# Board.net
KiCad netlist of a schematic drawn in EAGLE
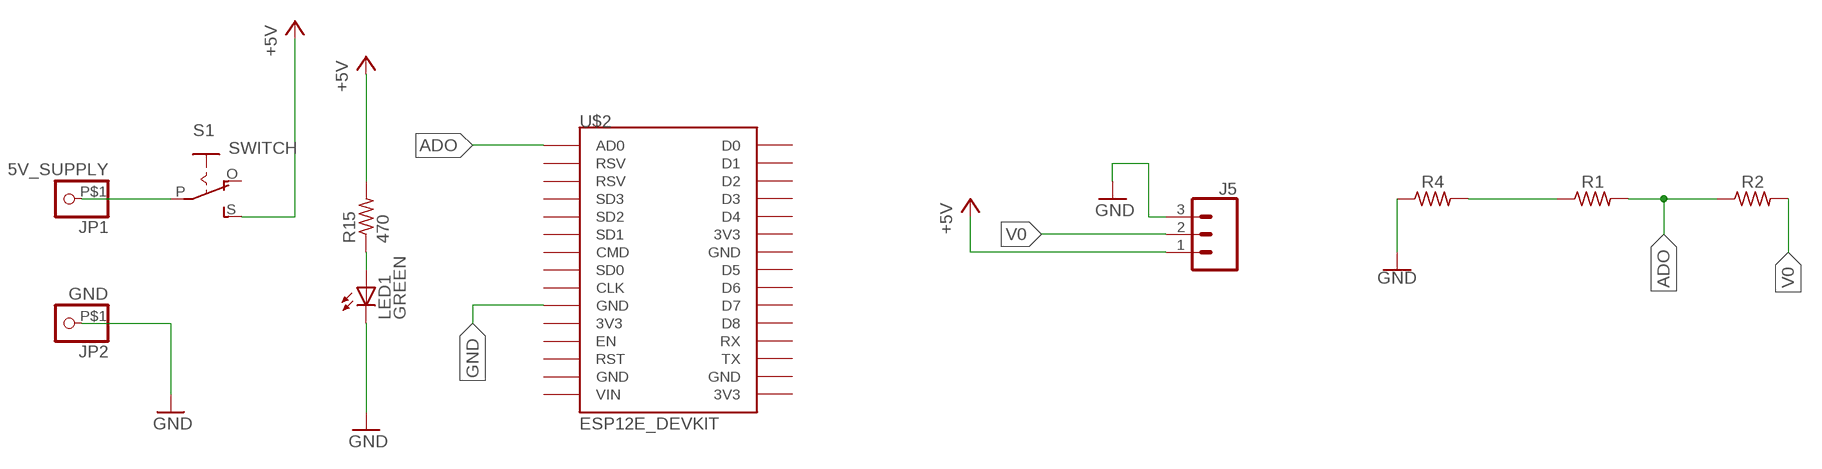
[diagram p0: schematic, sheet 1]

(export (version "E")
  (design (tool "Eeschema 10.0.6"))
  (components
    (comp (ref "J5")
      (value "1x3 RA Female .1\"")
      (footprint "eagle-import:1X03")
      (libsource (lib "eagle-import") (part "CONN_03"))
    )
    (comp (ref "JP1")
      (value "5V_SUPPLY")
      (footprint "eagle-import:1X1-BIGPOGO")
      (libsource (lib "eagle-import") (part "PINHD-1X1-BIGPOGO"))
    )
    (comp (ref "JP2")
      (value "GND")
      (footprint "eagle-import:1X1-BIGPOGO")
      (libsource (lib "eagle-import") (part "PINHD-1X1-BIGPOGO"))
    )
    (comp (ref "LED1")
      (value "GREEN")
      (footprint "eagle-import:LED5MM")
      (libsource (lib "eagle-import") (part "LED5MM"))
    )
    (comp (ref "R1")
      (value "101")
      (footprint "eagle-import:0207_12")
      (libsource (lib "eagle-import") (part "R-US_0207/12"))
    )
    (comp (ref "R2")
      (value "10k")
      (footprint "eagle-import:0207_12")
      (libsource (lib "eagle-import") (part "R-US_0207/12"))
    )
    (comp (ref "R4")
      (value "2.4k")
      (footprint "eagle-import:0207_12")
      (libsource (lib "eagle-import") (part "R-US_0207/12"))
    )
    (comp (ref "R15")
      (value "470")
      (footprint "eagle-import:0207_12")
      (libsource (lib "eagle-import") (part "R-US_0207/12"))
    )
    (comp (ref "S1")
      (value "SWITCH")
      (footprint "eagle-import:EG1218")
      (libsource (lib "eagle-import") (part "EG1218S"))
    )
    (comp (ref "U$2")
      (value "ESP12E_DEVKIT")
      (footprint "eagle-import:ESP12E_DEVKIT")
      (libsource (lib "eagle-import") (part "ESP12E_DEVKIT"))
    )
  )
  (nets
    (net (code "1") (name "+5V") (class "Default")
      (node (ref "J5") (pin "1") (pinfunction "1_1") (pintype "passive"))
      (node (ref "R15") (pin "2") (pinfunction "2_2") (pintype "passive"))
      (node (ref "S1") (pin "S") (pinfunction "S_S") (pintype "passive"))
    )
    (net (code "2") (name "ADO") (class "Default")
      (node (ref "R1") (pin "2") (pinfunction "2_2") (pintype "passive"))
      (node (ref "R2") (pin "1") (pinfunction "1_1") (pintype "passive"))
      (node (ref "U$2") (pin "AD0") (pinfunction "AD0_AD0") (pintype "bidirectional"))
    )
    (net (code "3") (name "GND") (class "Default")
      (node (ref "J5") (pin "3") (pinfunction "3_3") (pintype "passive"))
      (node (ref "JP2") (pin "P$1") (pinfunction "1_P$1") (pintype "passive"))
      (node (ref "LED1") (pin "K") (pinfunction "C_K") (pintype "passive"))
      (node (ref "R4") (pin "1") (pinfunction "1_1") (pintype "passive"))
      (node (ref "U$2") (pin "GND@0") (pinfunction "GND_GND@0") (pintype "bidirectional"))
    )
    (net (code "4") (name "Net-(JP1-1)") (class "Default")
      (node (ref "JP1") (pin "P$1") (pinfunction "1_P$1") (pintype "passive"))
      (node (ref "S1") (pin "P") (pinfunction "P_P") (pintype "passive"))
    )
    (net (code "5") (name "Net-(LED1-PadA)") (class "Default")
      (node (ref "LED1") (pin "A") (pinfunction "A_A") (pintype "passive"))
      (node (ref "R15") (pin "1") (pinfunction "1_1") (pintype "passive"))
    )
    (net (code "6") (name "Net-(R1-Pad1)") (class "Default")
      (node (ref "R1") (pin "1") (pinfunction "1_1") (pintype "passive"))
      (node (ref "R4") (pin "2") (pinfunction "2_2") (pintype "passive"))
    )
    (net (code "7") (name "V0") (class "Default")
      (node (ref "J5") (pin "2") (pinfunction "2_2") (pintype "passive"))
      (node (ref "R2") (pin "2") (pinfunction "2_2") (pintype "passive"))
    )
    (net (code "8") (name "unconnected-(S1-PadO)") (class "Default")
      (node (ref "S1") (pin "O") (pinfunction "O_O") (pintype "passive"))
    )
    (net (code "9") (name "unconnected-(U$2-3V3-Pad3V3@0)") (class "Default")
      (node (ref "U$2") (pin "3V3@0") (pinfunction "3V3_3V3@0") (pintype "bidirectional"))
    )
    (net (code "10") (name "unconnected-(U$2-3V3-Pad3V3@1)") (class "Default")
      (node (ref "U$2") (pin "3V3@1") (pinfunction "3V3_3V3@1") (pintype "bidirectional"))
    )
    (net (code "11") (name "unconnected-(U$2-3V3-Pad3V3@2)") (class "Default")
      (node (ref "U$2") (pin "3V3@2") (pinfunction "3V3_3V3@2") (pintype "bidirectional"))
    )
    (net (code "12") (name "unconnected-(U$2-GND-PadGND@1)") (class "Default")
      (node (ref "U$2") (pin "GND@1") (pinfunction "GND_GND@1") (pintype "bidirectional"))
    )
    (net (code "13") (name "unconnected-(U$2-GND-PadGND@2)") (class "Default")
      (node (ref "U$2") (pin "GND@2") (pinfunction "GND_GND@2") (pintype "bidirectional"))
    )
    (net (code "14") (name "unconnected-(U$2-GND-PadGND@3)") (class "Default")
      (node (ref "U$2") (pin "GND@3") (pinfunction "GND_GND@3") (pintype "bidirectional"))
    )
    (net (code "15") (name "unconnected-(U$2-PadCLK)") (class "Default")
      (node (ref "U$2") (pin "CLK") (pinfunction "CLK_CLK") (pintype "bidirectional"))
    )
    (net (code "16") (name "unconnected-(U$2-PadCMD)") (class "Default")
      (node (ref "U$2") (pin "CMD") (pinfunction "CMD_CMD") (pintype "bidirectional"))
    )
    (net (code "17") (name "unconnected-(U$2-PadD0)") (class "Default")
      (node (ref "U$2") (pin "D0") (pinfunction "D0_D0") (pintype "bidirectional"))
    )
    (net (code "18") (name "unconnected-(U$2-PadD1)") (class "Default")
      (node (ref "U$2") (pin "D1") (pinfunction "D1_D1") (pintype "bidirectional"))
    )
    (net (code "19") (name "unconnected-(U$2-PadD2)") (class "Default")
      (node (ref "U$2") (pin "D2") (pinfunction "D2_D2") (pintype "bidirectional"))
    )
    (net (code "20") (name "unconnected-(U$2-PadD3)") (class "Default")
      (node (ref "U$2") (pin "D3") (pinfunction "D3_D3") (pintype "bidirectional"))
    )
    (net (code "21") (name "unconnected-(U$2-PadD4)") (class "Default")
      (node (ref "U$2") (pin "D4") (pinfunction "D4_D4") (pintype "bidirectional"))
    )
    (net (code "22") (name "unconnected-(U$2-PadD5)") (class "Default")
      (node (ref "U$2") (pin "D5") (pinfunction "D5_D5") (pintype "bidirectional"))
    )
    (net (code "23") (name "unconnected-(U$2-PadD6)") (class "Default")
      (node (ref "U$2") (pin "D6") (pinfunction "D6_D6") (pintype "bidirectional"))
    )
    (net (code "24") (name "unconnected-(U$2-PadD7)") (class "Default")
      (node (ref "U$2") (pin "D7") (pinfunction "D7_D7") (pintype "bidirectional"))
    )
    (net (code "25") (name "unconnected-(U$2-PadD8)") (class "Default")
      (node (ref "U$2") (pin "D8") (pinfunction "D8_D8") (pintype "bidirectional"))
    )
    (net (code "26") (name "unconnected-(U$2-PadEN)") (class "Default")
      (node (ref "U$2") (pin "EN") (pinfunction "EN_EN") (pintype "bidirectional"))
    )
    (net (code "27") (name "unconnected-(U$2-PadRST)") (class "Default")
      (node (ref "U$2") (pin "RST") (pinfunction "RST_RST") (pintype "bidirectional"))
    )
    (net (code "28") (name "unconnected-(U$2-PadRX)") (class "Default")
      (node (ref "U$2") (pin "RX") (pinfunction "RX_RX") (pintype "bidirectional"))
    )
    (net (code "29") (name "unconnected-(U$2-PadSD0)") (class "Default")
      (node (ref "U$2") (pin "SD0") (pinfunction "SD0_SD0") (pintype "bidirectional"))
    )
    (net (code "30") (name "unconnected-(U$2-PadSD1)") (class "Default")
      (node (ref "U$2") (pin "SD1") (pinfunction "SD1_SD1") (pintype "bidirectional"))
    )
    (net (code "31") (name "unconnected-(U$2-PadSD2)") (class "Default")
      (node (ref "U$2") (pin "SD2") (pinfunction "SD2_SD2") (pintype "bidirectional"))
    )
    (net (code "32") (name "unconnected-(U$2-PadSD3)") (class "Default")
      (node (ref "U$2") (pin "SD3") (pinfunction "SD3_SD3") (pintype "bidirectional"))
    )
    (net (code "33") (name "unconnected-(U$2-PadTX)") (class "Default")
      (node (ref "U$2") (pin "TX") (pinfunction "TX_TX") (pintype "bidirectional"))
    )
    (net (code "34") (name "unconnected-(U$2-PadVIN)") (class "Default")
      (node (ref "U$2") (pin "VIN") (pinfunction "VIN_VIN") (pintype "bidirectional"))
    )
    (net (code "35") (name "unconnected-(U$2-RSV-PadRSV@0)") (class "Default")
      (node (ref "U$2") (pin "RSV@0") (pinfunction "RSV_RSV@0") (pintype "bidirectional"))
    )
    (net (code "36") (name "unconnected-(U$2-RSV-PadRSV@1)") (class "Default")
      (node (ref "U$2") (pin "RSV@1") (pinfunction "RSV_RSV@1") (pintype "bidirectional"))
    )
  )
)
